# Franzininho_CNC.net
KiCad netlist of a schematic drawn in EAGLE
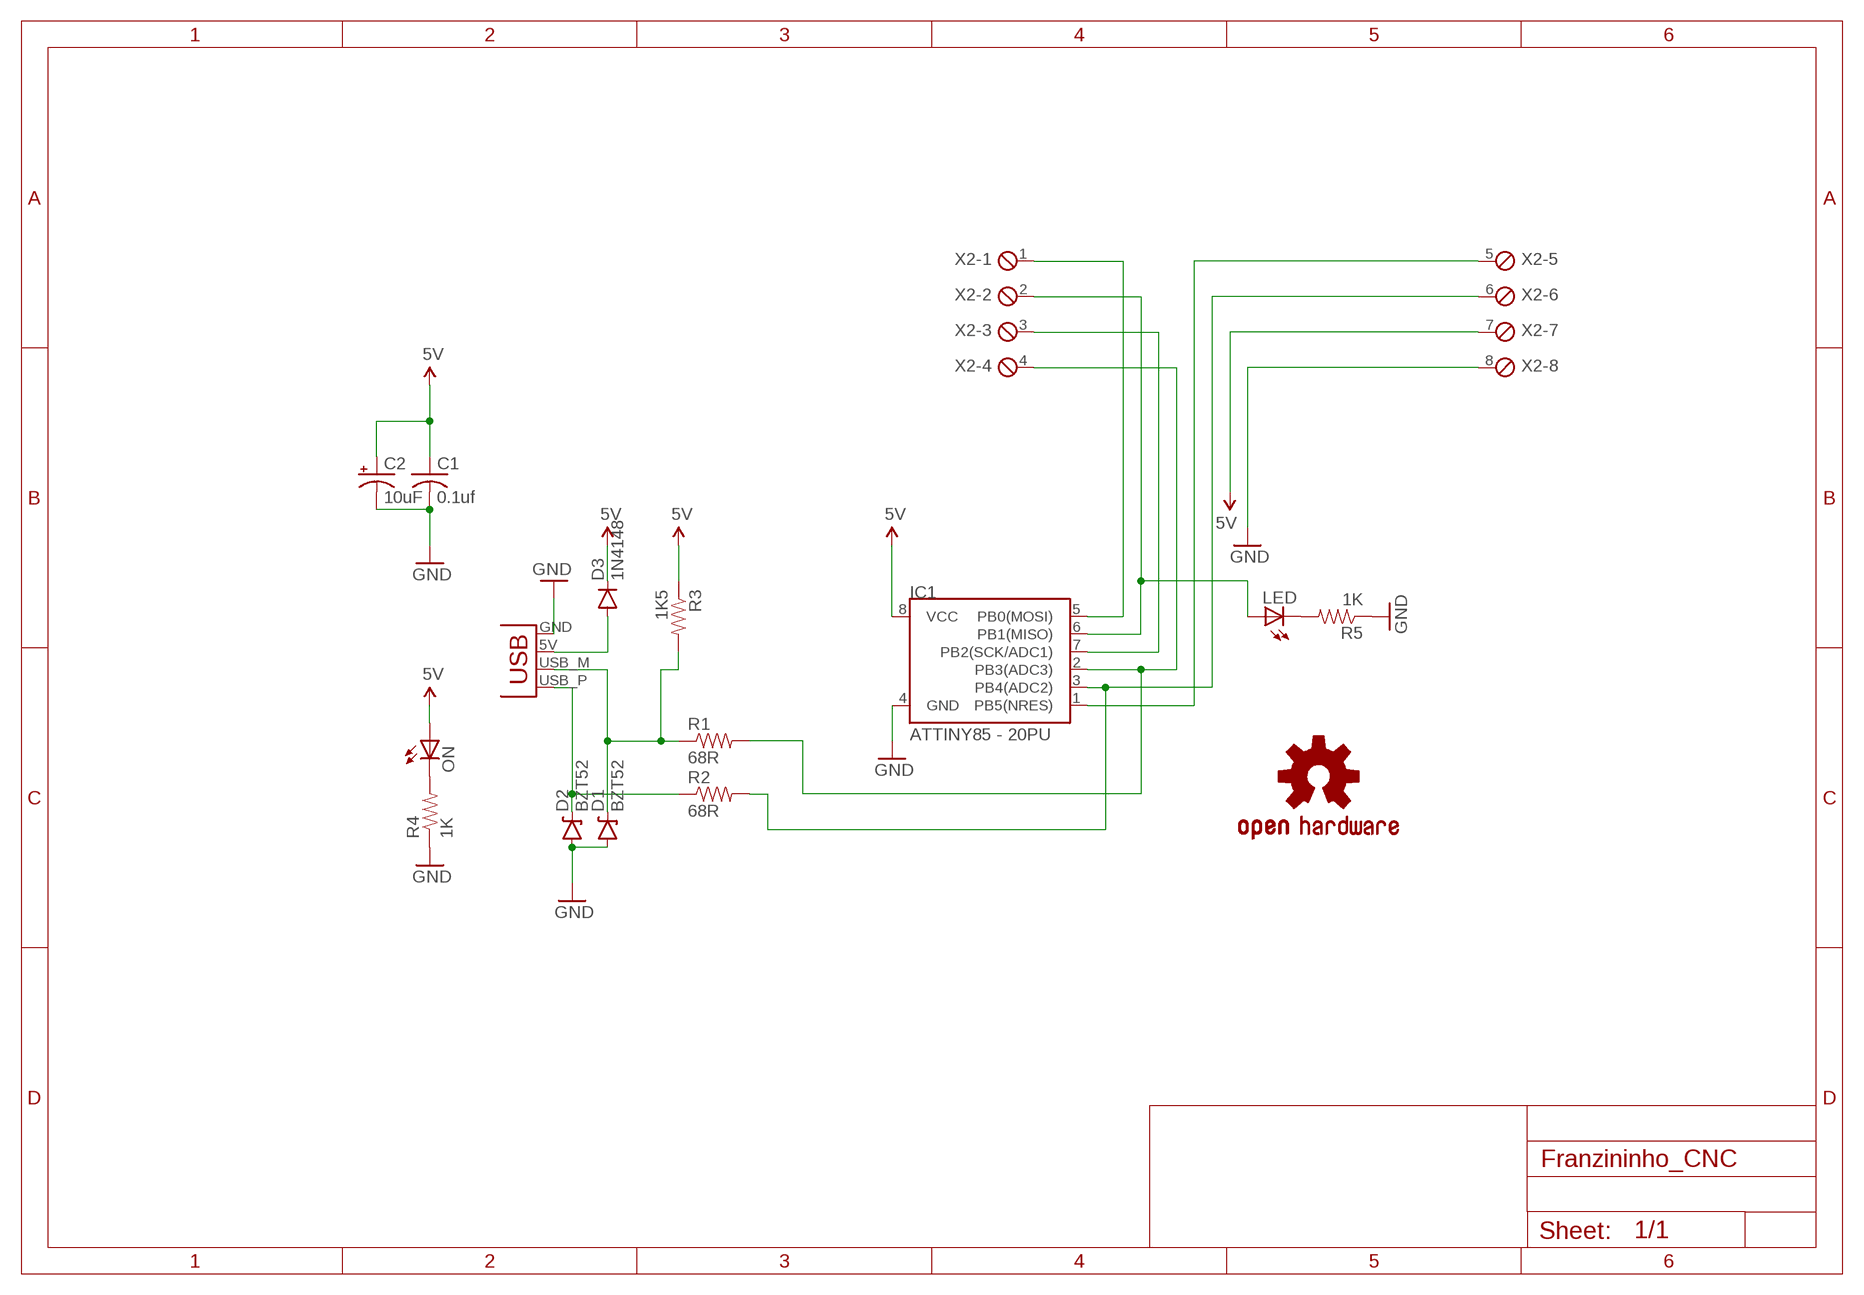
[diagram p0: schematic, sheet 1]

(export (version "E")
  (design (tool "Eeschema 10.0.6"))
  (components
    (comp (ref "C1")
      (value "0.1uf")
      (footprint "eagle-import:C025-025X050")
      (libsource (lib "eagle-import") (part "C-US025-025X050"))
    )
    (comp (ref "C2")
      (value "10uF")
      (footprint "eagle-import:E2,5-6E")
      (libsource (lib "eagle-import") (part "CPOL-USE2,5-6E"))
    )
    (comp (ref "D1")
      (value "BZT52")
      (footprint "eagle-import:DIODE-BZT52")
      (libsource (lib "eagle-import") (part "DIODE-ZENER"))
    )
    (comp (ref "D2")
      (value "BZT52")
      (footprint "eagle-import:DIODE-BZT52")
      (libsource (lib "eagle-import") (part "DIODE-ZENER"))
    )
    (comp (ref "D3")
      (value "1N4148")
      (footprint "eagle-import:DIODE-1N4148")
      (libsource (lib "eagle-import") (part "DIODE1N4148"))
    )
    (comp (ref "IC1")
      (value "ATTINY85 - 20PU")
      (footprint "eagle-import:DIP08")
      (libsource (lib "eagle-import") (part "ATTINY45TINY45-20-DIP"))
    )
    (comp (ref "LED")
      (value "LED3MM")
      (footprint "eagle-import:LED3MM")
      (libsource (lib "eagle-import") (part "LED3MM"))
    )
    (comp (ref "LOGO1")
      (value "OSHW-LOGOL")
      (footprint "eagle-import:OSHW-LOGO-L")
      (libsource (lib "eagle-import") (part "OSHW-LOGOL"))
    )
    (comp (ref "ON")
      (value "LED3MM")
      (footprint "eagle-import:LED3MM")
      (libsource (lib "eagle-import") (part "LED3MM"))
    )
    (comp (ref "R1")
      (value "68R")
      (footprint "eagle-import:AXIAL-0.4")
      (libsource (lib "eagle-import") (part "RESISTORPTH-1/4W"))
    )
    (comp (ref "R2")
      (value "68R")
      (footprint "eagle-import:AXIAL-0.4")
      (libsource (lib "eagle-import") (part "RESISTORPTH-1/4W"))
    )
    (comp (ref "R3")
      (value "1K5")
      (footprint "eagle-import:AXIAL-0.4")
      (libsource (lib "eagle-import") (part "RESISTORPTH-1/4W"))
    )
    (comp (ref "R4")
      (value "1K")
      (footprint "eagle-import:AXIAL-0.4")
      (libsource (lib "eagle-import") (part "RESISTORPTH-1/4W"))
    )
    (comp (ref "R5")
      (value "1K")
      (footprint "eagle-import:AXIAL-0.4")
      (libsource (lib "eagle-import") (part "RESISTORPTH-1/4W"))
    )
    (comp (ref "X1")
      (value "USBPCB")
      (footprint "eagle-import:USB-A-PCB")
      (libsource (lib "eagle-import") (part "USBPCB"))
    )
    (comp (ref "X2")
      (value "MPT8")
      (footprint "eagle-import:8POL254")
      (libsource (lib "eagle-import") (part "MPT8"))
    )
  )
  (nets
    (net (code "1") (name "5V") (class "Default")
      (node (ref "C1") (pin "1") (pinfunction "1_1") (pintype "passive"))
      (node (ref "C2") (pin "+") (pinfunction "+_+") (pintype "passive"))
      (node (ref "D3") (pin "C") (pinfunction "C_C") (pintype "passive"))
      (node (ref "IC1") (pin "8") (pinfunction "VCC_8") (pintype "bidirectional"))
      (node (ref "ON") (pin "A") (pinfunction "A_A") (pintype "passive"))
      (node (ref "R3") (pin "P$1") (pinfunction "1_P$1") (pintype "passive"))
      (node (ref "X2") (pin "7") (pinfunction "1_7") (pintype "passive"))
    )
    (net (code "2") (name "GND") (class "Default")
      (node (ref "C1") (pin "2") (pinfunction "2_2") (pintype "passive"))
      (node (ref "C2") (pin "-") (pinfunction "-_-") (pintype "passive"))
      (node (ref "D1") (pin "A") (pinfunction "A_A") (pintype "passive"))
      (node (ref "D2") (pin "A") (pinfunction "A_A") (pintype "passive"))
      (node (ref "IC1") (pin "4") (pinfunction "GND_4") (pintype "bidirectional"))
      (node (ref "R4") (pin "P$1") (pinfunction "1_P$1") (pintype "passive"))
      (node (ref "R5") (pin "P$1") (pinfunction "1_P$1") (pintype "passive"))
      (node (ref "X1") (pin "GND") (pinfunction "GND_GND") (pintype "bidirectional"))
      (node (ref "X2") (pin "8") (pinfunction "1_8") (pintype "passive"))
    )
    (net (code "3") (name "Net-(IC1-PB0(MOSI))") (class "Default")
      (node (ref "IC1") (pin "5") (pinfunction "PB0(MOSI)_5") (pintype "bidirectional"))
      (node (ref "X2") (pin "1") (pinfunction "1_1") (pintype "passive"))
    )
    (net (code "4") (name "Net-(IC1-PB1(MISO))") (class "Default")
      (node (ref "IC1") (pin "6") (pinfunction "PB1(MISO)_6") (pintype "bidirectional"))
      (node (ref "LED") (pin "A") (pinfunction "A_A") (pintype "passive"))
      (node (ref "X2") (pin "2") (pinfunction "1_2") (pintype "passive"))
    )
    (net (code "5") (name "Net-(IC1-PB2(SCK{slash}ADC1))") (class "Default")
      (node (ref "IC1") (pin "7") (pinfunction "PB2(SCK/ADC1)_7") (pintype "bidirectional"))
      (node (ref "X2") (pin "3") (pinfunction "1_3") (pintype "passive"))
    )
    (net (code "6") (name "Net-(IC1-PB3(ADC3))") (class "Default")
      (node (ref "IC1") (pin "2") (pinfunction "PB3(ADC3)_2") (pintype "bidirectional"))
      (node (ref "R1") (pin "P$2") (pinfunction "2_P$2") (pintype "passive"))
      (node (ref "X2") (pin "4") (pinfunction "1_4") (pintype "passive"))
    )
    (net (code "7") (name "Net-(IC1-PB4(ADC2))") (class "Default")
      (node (ref "IC1") (pin "3") (pinfunction "PB4(ADC2)_3") (pintype "bidirectional"))
      (node (ref "R2") (pin "P$2") (pinfunction "2_P$2") (pintype "passive"))
      (node (ref "X2") (pin "6") (pinfunction "1_6") (pintype "passive"))
    )
    (net (code "8") (name "Net-(IC1-PB5(NRES))") (class "Default")
      (node (ref "IC1") (pin "1") (pinfunction "PB5(NRES)_1") (pintype "bidirectional"))
      (node (ref "X2") (pin "5") (pinfunction "1_5") (pintype "passive"))
    )
    (net (code "9") (name "Net-(LED-C)") (class "Default")
      (node (ref "LED") (pin "K") (pinfunction "C_K") (pintype "passive"))
      (node (ref "R5") (pin "P$2") (pinfunction "2_P$2") (pintype "passive"))
    )
    (net (code "10") (name "Net-(ON-C)") (class "Default")
      (node (ref "ON") (pin "K") (pinfunction "C_K") (pintype "passive"))
      (node (ref "R4") (pin "P$2") (pinfunction "2_P$2") (pintype "passive"))
    )
    (net (code "11") (name "Net-(R1-1)") (class "Default")
      (node (ref "D1") (pin "C") (pinfunction "C_C") (pintype "passive"))
      (node (ref "R1") (pin "P$1") (pinfunction "1_P$1") (pintype "passive"))
      (node (ref "R3") (pin "P$2") (pinfunction "2_P$2") (pintype "passive"))
      (node (ref "X1") (pin "USB_M") (pinfunction "D-_USB_M") (pintype "bidirectional"))
    )
    (net (code "12") (name "Net-(R2-1)") (class "Default")
      (node (ref "D2") (pin "C") (pinfunction "C_C") (pintype "passive"))
      (node (ref "R2") (pin "P$1") (pinfunction "1_P$1") (pintype "passive"))
      (node (ref "X1") (pin "USB_P") (pinfunction "D+_USB_P") (pintype "bidirectional"))
    )
    (net (code "13") (name "Net-(X1-VBUS)") (class "Default")
      (node (ref "D3") (pin "A") (pinfunction "A_A") (pintype "passive"))
      (node (ref "X1") (pin "5V") (pinfunction "VBUS_5V") (pintype "bidirectional"))
    )
  )
)
